# working.net
KiCad netlist of a schematic drawn in EAGLE
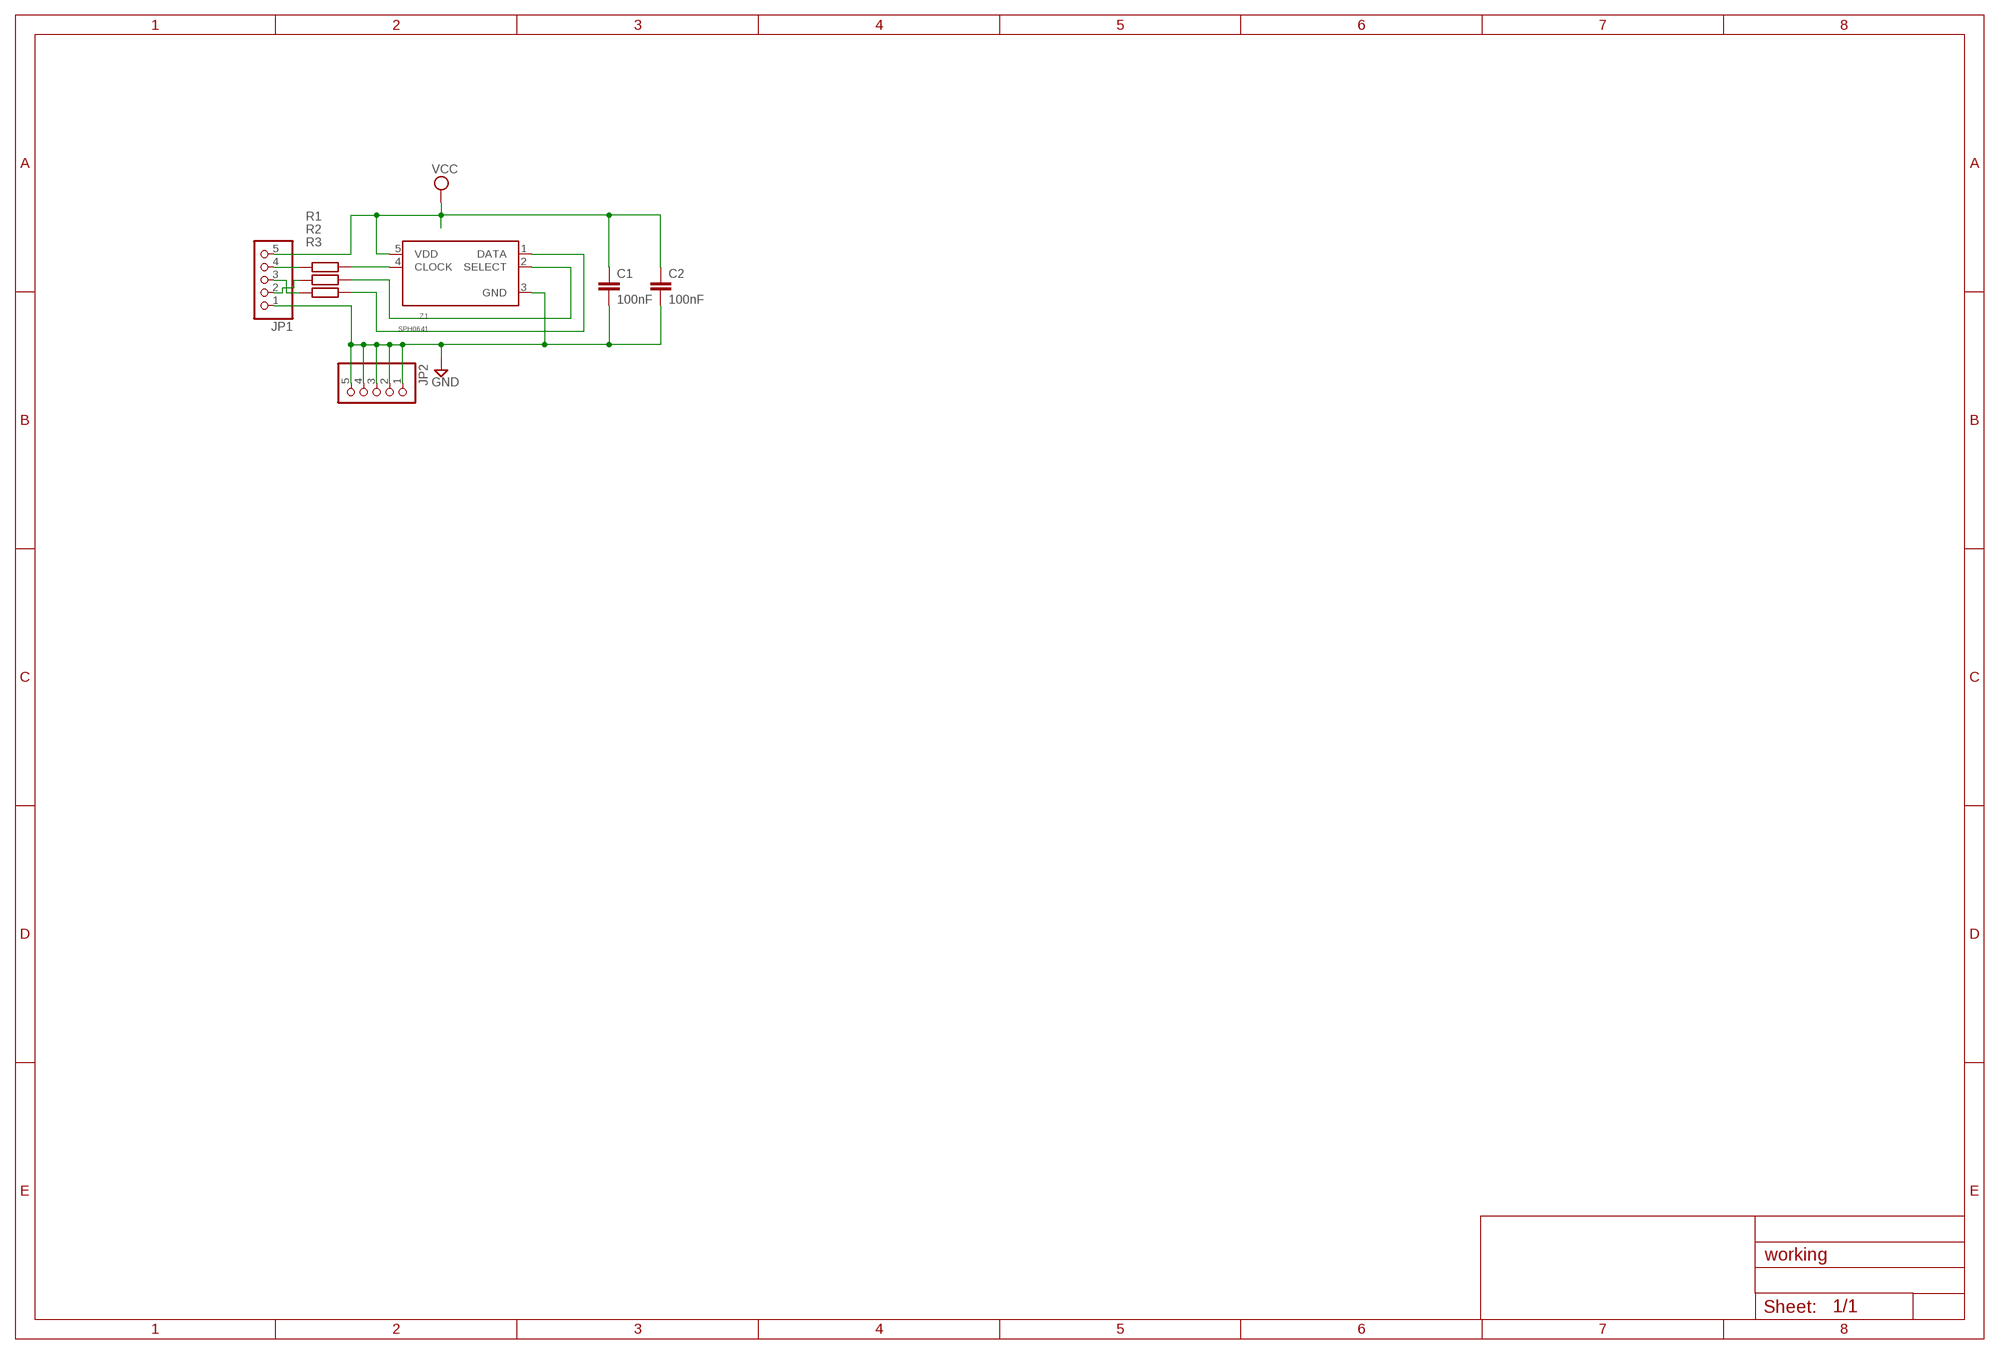
[diagram p0: schematic, sheet 1]

(export (version "E")
  (design (tool "Eeschema 10.0.6"))
  (components
    (comp (ref "C1")
      (value "100nF")
      (footprint "eagle-import:C0805K")
      (libsource (lib "eagle-import") (part "C-EUC0805K"))
    )
    (comp (ref "C2")
      (value "100nF")
      (footprint "eagle-import:C0805K")
      (libsource (lib "eagle-import") (part "C-EUC0805K"))
    )
    (comp (ref "JP1")
      (value "PINHD-1X5")
      (footprint "eagle-import:1X05")
      (libsource (lib "eagle-import") (part "PINHD-1X5"))
    )
    (comp (ref "JP2")
      (value "PINHD-1X5")
      (footprint "eagle-import:1X05")
      (libsource (lib "eagle-import") (part "PINHD-1X5"))
    )
    (comp (ref "R1")
      (value "R-EU_R0603")
      (footprint "eagle-import:R0603")
      (libsource (lib "eagle-import") (part "R-EU_R0603"))
    )
    (comp (ref "R2")
      (value "R-EU_R0603")
      (footprint "eagle-import:R0603")
      (libsource (lib "eagle-import") (part "R-EU_R0603"))
    )
    (comp (ref "R3")
      (value "R-EU_R0603")
      (footprint "eagle-import:R0603")
      (libsource (lib "eagle-import") (part "R-EU_R0603"))
    )
    (comp (ref "Z1")
      (value "SPH0641")
      (footprint "eagle-import:SPH0641")
      (libsource (lib "eagle-import") (part "SPH0641"))
    )
  )
  (nets
    (net (code "1") (name "GND") (class "Default")
      (node (ref "C1") (pin "2") (pinfunction "2_2") (pintype "passive"))
      (node (ref "C2") (pin "2") (pinfunction "2_2") (pintype "passive"))
      (node (ref "JP1") (pin "1") (pinfunction "1_1") (pintype "passive"))
      (node (ref "JP2") (pin "1") (pinfunction "1_1") (pintype "passive"))
      (node (ref "JP2") (pin "2") (pinfunction "2_2") (pintype "passive"))
      (node (ref "JP2") (pin "3") (pinfunction "3_3") (pintype "passive"))
      (node (ref "JP2") (pin "4") (pinfunction "4_4") (pintype "passive"))
      (node (ref "JP2") (pin "5") (pinfunction "5_5") (pintype "passive"))
      (node (ref "Z1") (pin "3") (pinfunction "GND_3") (pintype "bidirectional"))
    )
    (net (code "2") (name "Net-(JP1-Pad2)") (class "Default")
      (node (ref "JP1") (pin "2") (pinfunction "2_2") (pintype "passive"))
      (node (ref "R2") (pin "1") (pinfunction "1_1") (pintype "passive"))
    )
    (net (code "3") (name "Net-(JP1-Pad3)") (class "Default")
      (node (ref "JP1") (pin "3") (pinfunction "3_3") (pintype "passive"))
      (node (ref "R3") (pin "1") (pinfunction "1_1") (pintype "passive"))
    )
    (net (code "4") (name "Net-(JP1-Pad4)") (class "Default")
      (node (ref "JP1") (pin "4") (pinfunction "4_4") (pintype "passive"))
      (node (ref "R1") (pin "1") (pinfunction "1_1") (pintype "passive"))
    )
    (net (code "5") (name "Net-(Z1-CLOCK)") (class "Default")
      (node (ref "R1") (pin "2") (pinfunction "2_2") (pintype "passive"))
      (node (ref "Z1") (pin "4") (pinfunction "CLOCK_4") (pintype "bidirectional"))
    )
    (net (code "6") (name "Net-(Z1-DATA)") (class "Default")
      (node (ref "R3") (pin "2") (pinfunction "2_2") (pintype "passive"))
      (node (ref "Z1") (pin "1") (pinfunction "DATA_1") (pintype "bidirectional"))
    )
    (net (code "7") (name "Net-(Z1-SELECT)") (class "Default")
      (node (ref "R2") (pin "2") (pinfunction "2_2") (pintype "passive"))
      (node (ref "Z1") (pin "2") (pinfunction "SELECT_2") (pintype "bidirectional"))
    )
    (net (code "8") (name "VCC") (class "Default")
      (node (ref "C1") (pin "1") (pinfunction "1_1") (pintype "passive"))
      (node (ref "C2") (pin "1") (pinfunction "1_1") (pintype "passive"))
      (node (ref "JP1") (pin "5") (pinfunction "5_5") (pintype "passive"))
      (node (ref "Z1") (pin "5") (pinfunction "VDD_5") (pintype "bidirectional"))
    )
  )
)
